# Processor.net
KiCad netlist of a schematic drawn in Altium Designer
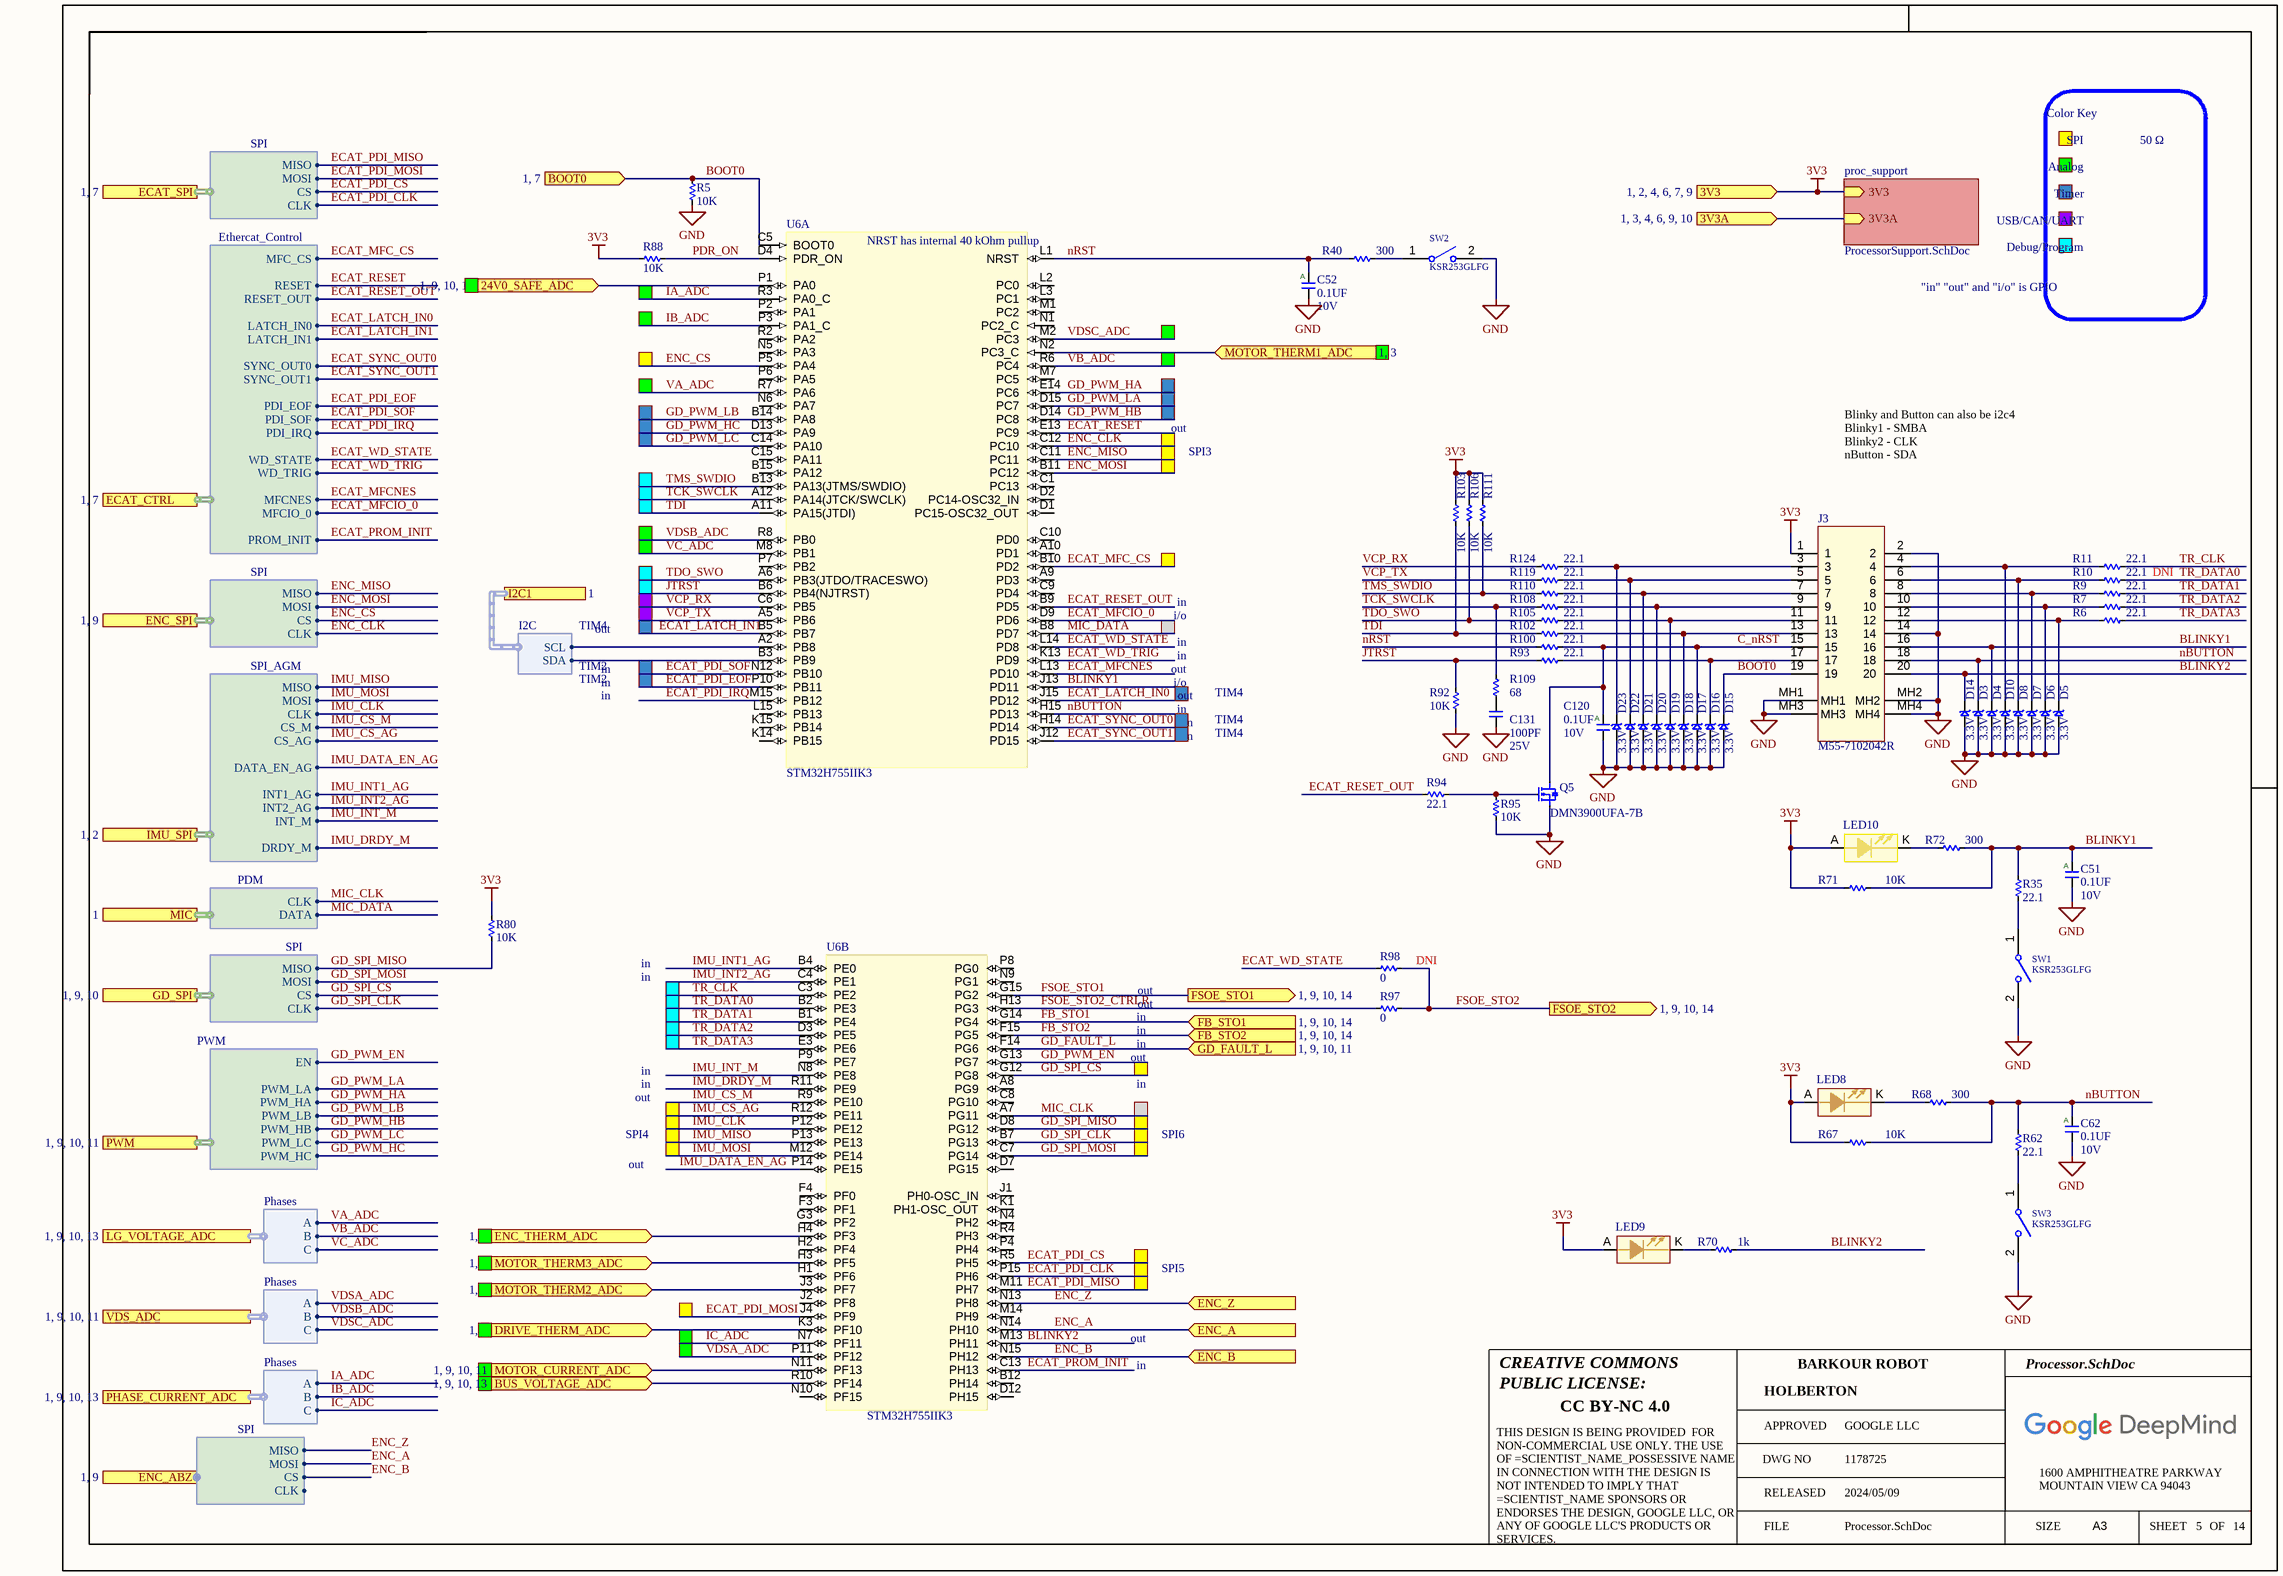
[diagram p0: Processor.SchDoc]

(export (version "E")
  (design (tool "Eeschema 10.0.6"))
  (components
    (comp (ref "C51")
      (value "0.1UF")
      (footprint "C0201")
      (description "CAP, CER, X6S, 0.1uF, 10V, 10%, 0201, AUTOGRADE")
      (fields
        (field (name "MFG") "MURATA")
        (field (name "VOLTAGE") "10V")
        (field (name "Comment") "__Template_Cap_Auto")
      )
      (libsource (lib "AltiumReleaseLibDB") (part "__Template_Cap_Auto"))
    )
    (comp (ref "C52")
      (value "0.1UF")
      (footprint "C0201")
      (description "CAP, CER, X6S, 0.1uF, 10V, 10%, 0201, AUTOGRADE")
      (fields
        (field (name "MFG") "MURATA")
        (field (name "VOLTAGE") "10V")
        (field (name "Comment") "__Template_Cap_Auto")
      )
      (libsource (lib "AltiumReleaseLibDB") (part "__Template_Cap_Auto"))
    )
    (comp (ref "C62")
      (value "0.1UF")
      (footprint "C0201")
      (description "CAP, CER, X6S, 0.1uF, 10V, 10%, 0201, AUTOGRADE")
      (fields
        (field (name "MFG") "MURATA")
        (field (name "VOLTAGE") "10V")
        (field (name "Comment") "__Template_Cap_Auto")
      )
      (libsource (lib "AltiumReleaseLibDB") (part "__Template_Cap_Auto"))
    )
    (comp (ref "C120")
      (value "0.1UF")
      (footprint "C0201")
      (description "CAP, CER, X6S, 0.1uF, 10V, 10%, 0201, AUTOGRADE")
      (fields
        (field (name "MFG") "MURATA")
        (field (name "VOLTAGE") "10V")
        (field (name "Comment") "__Template_Cap_Auto")
      )
      (libsource (lib "AltiumReleaseLibDB") (part "__Template_Cap_Auto"))
    )
    (comp (ref "C131")
      (value "100PF")
      (footprint "C0201")
      (description "CAP, CER, X7R, 100pF, 25V, 10%, 0201, 0.33mm T")
      (fields
        (field (name "MFG") "MURATA")
        (field (name "VOLTAGE") "25V")
        (field (name "Comment") "__Template_Cap")
      )
      (libsource (lib "AltiumReleaseLibDB") (part "__Template_Cap"))
    )
    (comp (ref "D3")
      (value "3.3V")
      (footprint "SOD1060X40")
      (description "TVS, DIODE, UNIDIR, 3.3VRWM, 4.8VBR, 7.8VCL, SOD-923")
      (fields (field (name "MFG") "ON Semiconductor"))
      (libsource (lib "AltiumReleaseLibDB") (part "__Template_Diode_TVS_A/K"))
    )
    (comp (ref "D4")
      (value "3.3V")
      (footprint "SOD1060X40")
      (description "TVS, DIODE, UNIDIR, 3.3VRWM, 4.8VBR, 7.8VCL, SOD-923")
      (fields (field (name "MFG") "ON Semiconductor"))
      (libsource (lib "AltiumReleaseLibDB") (part "__Template_Diode_TVS_A/K"))
    )
    (comp (ref "D5")
      (value "3.3V")
      (footprint "SOD1060X40")
      (description "TVS, DIODE, UNIDIR, 3.3VRWM, 4.8VBR, 7.8VCL, SOD-923")
      (fields (field (name "MFG") "ON Semiconductor"))
      (libsource (lib "AltiumReleaseLibDB") (part "__Template_Diode_TVS_A/K"))
    )
    (comp (ref "D6")
      (value "3.3V")
      (footprint "SOD1060X40")
      (description "TVS, DIODE, UNIDIR, 3.3VRWM, 4.8VBR, 7.8VCL, SOD-923")
      (fields (field (name "MFG") "ON Semiconductor"))
      (libsource (lib "AltiumReleaseLibDB") (part "__Template_Diode_TVS_A/K"))
    )
    (comp (ref "D7")
      (value "3.3V")
      (footprint "SOD1060X40")
      (description "TVS, DIODE, UNIDIR, 3.3VRWM, 4.8VBR, 7.8VCL, SOD-923")
      (fields (field (name "MFG") "ON Semiconductor"))
      (libsource (lib "AltiumReleaseLibDB") (part "__Template_Diode_TVS_A/K"))
    )
    (comp (ref "D8")
      (value "3.3V")
      (footprint "SOD1060X40")
      (description "TVS, DIODE, UNIDIR, 3.3VRWM, 4.8VBR, 7.8VCL, SOD-923")
      (fields (field (name "MFG") "ON Semiconductor"))
      (libsource (lib "AltiumReleaseLibDB") (part "__Template_Diode_TVS_A/K"))
    )
    (comp (ref "D10")
      (value "3.3V")
      (footprint "SOD1060X40")
      (description "TVS, DIODE, UNIDIR, 3.3VRWM, 4.8VBR, 7.8VCL, SOD-923")
      (fields (field (name "MFG") "ON Semiconductor"))
      (libsource (lib "AltiumReleaseLibDB") (part "__Template_Diode_TVS_A/K"))
    )
    (comp (ref "D14")
      (value "3.3V")
      (footprint "SOD1060X40")
      (description "TVS, DIODE, UNIDIR, 3.3VRWM, 4.8VBR, 7.8VCL, SOD-923")
      (fields (field (name "MFG") "ON Semiconductor"))
      (libsource (lib "AltiumReleaseLibDB") (part "__Template_Diode_TVS_A/K"))
    )
    (comp (ref "D15")
      (value "3.3V")
      (footprint "SOD1060X40")
      (description "TVS, DIODE, UNIDIR, 3.3VRWM, 4.8VBR, 7.8VCL, SOD-923")
      (fields (field (name "MFG") "ON Semiconductor"))
      (libsource (lib "AltiumReleaseLibDB") (part "__Template_Diode_TVS_A/K"))
    )
    (comp (ref "D16")
      (value "3.3V")
      (footprint "SOD1060X40")
      (description "TVS, DIODE, UNIDIR, 3.3VRWM, 4.8VBR, 7.8VCL, SOD-923")
      (fields (field (name "MFG") "ON Semiconductor"))
      (libsource (lib "AltiumReleaseLibDB") (part "__Template_Diode_TVS_A/K"))
    )
    (comp (ref "D17")
      (value "3.3V")
      (footprint "SOD1060X40")
      (description "TVS, DIODE, UNIDIR, 3.3VRWM, 4.8VBR, 7.8VCL, SOD-923")
      (fields (field (name "MFG") "ON Semiconductor"))
      (libsource (lib "AltiumReleaseLibDB") (part "__Template_Diode_TVS_A/K"))
    )
    (comp (ref "D18")
      (value "3.3V")
      (footprint "SOD1060X40")
      (description "TVS, DIODE, UNIDIR, 3.3VRWM, 4.8VBR, 7.8VCL, SOD-923")
      (fields (field (name "MFG") "ON Semiconductor"))
      (libsource (lib "AltiumReleaseLibDB") (part "__Template_Diode_TVS_A/K"))
    )
    (comp (ref "D19")
      (value "3.3V")
      (footprint "SOD1060X40")
      (description "TVS, DIODE, UNIDIR, 3.3VRWM, 4.8VBR, 7.8VCL, SOD-923")
      (fields (field (name "MFG") "ON Semiconductor"))
      (libsource (lib "AltiumReleaseLibDB") (part "__Template_Diode_TVS_A/K"))
    )
    (comp (ref "D20")
      (value "3.3V")
      (footprint "SOD1060X40")
      (description "TVS, DIODE, UNIDIR, 3.3VRWM, 4.8VBR, 7.8VCL, SOD-923")
      (fields (field (name "MFG") "ON Semiconductor"))
      (libsource (lib "AltiumReleaseLibDB") (part "__Template_Diode_TVS_A/K"))
    )
    (comp (ref "D21")
      (value "3.3V")
      (footprint "SOD1060X40")
      (description "TVS, DIODE, UNIDIR, 3.3VRWM, 4.8VBR, 7.8VCL, SOD-923")
      (fields (field (name "MFG") "ON Semiconductor"))
      (libsource (lib "AltiumReleaseLibDB") (part "__Template_Diode_TVS_A/K"))
    )
    (comp (ref "D22")
      (value "3.3V")
      (footprint "SOD1060X40")
      (description "TVS, DIODE, UNIDIR, 3.3VRWM, 4.8VBR, 7.8VCL, SOD-923")
      (fields (field (name "MFG") "ON Semiconductor"))
      (libsource (lib "AltiumReleaseLibDB") (part "__Template_Diode_TVS_A/K"))
    )
    (comp (ref "D23")
      (value "3.3V")
      (footprint "SOD1060X40")
      (description "TVS, DIODE, UNIDIR, 3.3VRWM, 4.8VBR, 7.8VCL, SOD-923")
      (fields (field (name "MFG") "ON Semiconductor"))
      (libsource (lib "AltiumReleaseLibDB") (part "__Template_Diode_TVS_A/K"))
    )
    (comp (ref "J3")
      (value "M55-7102042R")
      (footprint "CON_M55-7102042R")
      (description "CONN HEADER SMD R/A 20POS 1.27MM")
      (fields (field (name "MFG") "Harwin Inc.") (field (name "MFG P/N") "M55-7102042R"))
      (libsource (lib "AltiumReleaseLibDB") (part "__Template_Connector_2X10_4MH"))
    )
    (comp (ref "LED8")
      (value "__Template_LED_ORANGE_AK")
      (footprint "LED_APG0603SYC-TT")
      (description "LED, ORANGE, 611NM, 10mA, CLEAR, 0201")
      (fields (field (name "MFG") "Kingbright"))
      (libsource (lib "AltiumReleaseLibDB") (part "__Template_LED_ORANGE_AK"))
    )
    (comp (ref "LED9")
      (value "__Template_LED_ORANGE_AK")
      (footprint "LED_APG0603SYC-TT")
      (description "LED, ORANGE, 611NM, 10mA, CLEAR, 0201")
      (fields (field (name "MFG") "Kingbright"))
      (libsource (lib "AltiumReleaseLibDB") (part "__Template_LED_ORANGE_AK"))
    )
    (comp (ref "LED10")
      (value "__Template_LED_YELLOW_AK")
      (footprint "LED_APG0603SYC-TT")
      (description "LED, YELLOW, 591NM, 10mA, CLEAR, 0201")
      (fields (field (name "MFG") "Kingbright"))
      (libsource (lib "AltiumReleaseLibDB") (part "__Template_LED_YELLOW_AK"))
    )
    (comp (ref "Q5")
      (value "NFET_DMN3900UFA")
      (footprint "3XDFN")
      (description "MOSFET, N-CH, 30V, 0.55A, DMN3900")
      (fields (field (name "MFG") "Diodes Incorporated") (field (name "MFG P/N") "DMN3900UFA-7B"))
      (libsource (lib "AltiumReleaseLibDB") (part "NFET_DMN3900UFA"))
    )
    (comp (ref "R5")
      (value "10K")
      (footprint "R0201")
      (description "RES, 10K, 1%, 1/20W, 0201, AUTOGRADE")
      (fields (field (name "MFG") "PANASONIC") (field (name "Comment") "__Template_Resistor"))
      (libsource (lib "AltiumReleaseLibDB") (part "__Template_Resistor"))
    )
    (comp (ref "R6")
      (value "22.1")
      (footprint "R0201")
      (description "RES, 22.1, 1%, 1/20W, 0201, AUTOGRADE")
      (fields
        (field (name "MFG") "Panasonic Electronic Components")
        (field (name "Comment") "__Template_Resistor")
      )
      (libsource (lib "AltiumReleaseLibDB") (part "__Template_Resistor"))
    )
    (comp (ref "R7")
      (value "22.1")
      (footprint "R0201")
      (description "RES, 22.1, 1%, 1/20W, 0201, AUTOGRADE")
      (fields
        (field (name "MFG") "Panasonic Electronic Components")
        (field (name "Comment") "__Template_Resistor")
      )
      (libsource (lib "AltiumReleaseLibDB") (part "__Template_Resistor"))
    )
    (comp (ref "R9")
      (value "22.1")
      (footprint "R0201")
      (description "RES, 22.1, 1%, 1/20W, 0201, AUTOGRADE")
      (fields
        (field (name "MFG") "Panasonic Electronic Components")
        (field (name "Comment") "__Template_Resistor")
      )
      (libsource (lib "AltiumReleaseLibDB") (part "__Template_Resistor"))
    )
    (comp (ref "R10")
      (value "22.1")
      (footprint "R0201")
      (description "RES, 22.1, 1%, 1/20W, 0201, AUTOGRADE")
      (fields
        (field (name "MFG") "Panasonic Electronic Components")
        (field (name "DNI") "DNI")
        (field (name "Comment") "__Template_Resistor")
      )
      (libsource (lib "AltiumReleaseLibDB") (part "__Template_Resistor"))
    )
    (comp (ref "R11")
      (value "22.1")
      (footprint "R0201")
      (description "RES, 22.1, 1%, 1/20W, 0201, AUTOGRADE")
      (fields
        (field (name "MFG") "Panasonic Electronic Components")
        (field (name "Comment") "__Template_Resistor")
      )
      (libsource (lib "AltiumReleaseLibDB") (part "__Template_Resistor"))
    )
    (comp (ref "R35")
      (value "22.1")
      (footprint "R0201")
      (description "RES, 22.1, 1%, 1/20W, 0201, AUTOGRADE")
      (fields
        (field (name "MFG") "Panasonic Electronic Components")
        (field (name "Comment") "__Template_Resistor")
      )
      (libsource (lib "AltiumReleaseLibDB") (part "__Template_Resistor"))
    )
    (comp (ref "R40")
      (value "300")
      (footprint "R0201")
      (description "RES, 300, 1%, 1/20W, 0201, AUTOGRADE")
      (fields
        (field (name "MFG") "Panasonic Electronic Components")
        (field (name "Comment") "__Template_Resistor")
      )
      (libsource (lib "AltiumReleaseLibDB") (part "__Template_Resistor"))
    )
    (comp (ref "R62")
      (value "22.1")
      (footprint "R0201")
      (description "RES, 22.1, 1%, 1/20W, 0201, AUTOGRADE")
      (fields
        (field (name "MFG") "Panasonic Electronic Components")
        (field (name "Comment") "__Template_Resistor")
      )
      (libsource (lib "AltiumReleaseLibDB") (part "__Template_Resistor"))
    )
    (comp (ref "R67")
      (value "10K")
      (footprint "R0201")
      (description "RES, 10K, 1%, 1/20W, 0201, AUTOGRADE")
      (fields (field (name "MFG") "PANASONIC") (field (name "Comment") "__Template_Resistor"))
      (libsource (lib "AltiumReleaseLibDB") (part "__Template_Resistor"))
    )
    (comp (ref "R68")
      (value "300")
      (footprint "R0201")
      (description "RES, 300, 1%, 1/20W, 0201, AUTOGRADE")
      (fields
        (field (name "MFG") "Panasonic Electronic Components")
        (field (name "Comment") "__Template_Resistor")
      )
      (libsource (lib "AltiumReleaseLibDB") (part "__Template_Resistor"))
    )
    (comp (ref "R70")
      (value "1k")
      (footprint "R0201")
      (description "RES, 1K, 1%, 1/20W, 0201, AUTOGRADE")
      (fields (field (name "MFG") "Bourns Inc.") (field (name "Comment") "__Template_Resistor"))
      (libsource (lib "AltiumReleaseLibDB") (part "__Template_Resistor"))
    )
    (comp (ref "R71")
      (value "10K")
      (footprint "R0201")
      (description "RES, 10K, 1%, 1/20W, 0201, AUTOGRADE")
      (fields (field (name "MFG") "PANASONIC") (field (name "Comment") "__Template_Resistor"))
      (libsource (lib "AltiumReleaseLibDB") (part "__Template_Resistor"))
    )
    (comp (ref "R72")
      (value "300")
      (footprint "R0201")
      (description "RES, 300, 1%, 1/20W, 0201, AUTOGRADE")
      (fields
        (field (name "MFG") "Panasonic Electronic Components")
        (field (name "Comment") "__Template_Resistor")
      )
      (libsource (lib "AltiumReleaseLibDB") (part "__Template_Resistor"))
    )
    (comp (ref "R80")
      (value "10K")
      (footprint "R0201")
      (description "RES, 10K, 1%, 1/20W, 0201, AUTOGRADE")
      (fields (field (name "MFG") "PANASONIC") (field (name "Comment") "__Template_Resistor"))
      (libsource (lib "AltiumReleaseLibDB") (part "__Template_Resistor"))
    )
    (comp (ref "R88")
      (value "10K")
      (footprint "R0201")
      (description "RES, 10K, 1%, 1/20W, 0201, AUTOGRADE")
      (fields (field (name "MFG") "PANASONIC") (field (name "Comment") "__Template_Resistor"))
      (libsource (lib "AltiumReleaseLibDB") (part "__Template_Resistor"))
    )
    (comp (ref "R92")
      (value "10K")
      (footprint "R0201")
      (description "RES, 10K, 1%, 1/20W, 0201, AUTOGRADE")
      (fields (field (name "MFG") "PANASONIC") (field (name "Comment") "__Template_Resistor"))
      (libsource (lib "AltiumReleaseLibDB") (part "__Template_Resistor"))
    )
    (comp (ref "R93")
      (value "22.1")
      (footprint "R0201")
      (description "RES, 22.1, 1%, 1/20W, 0201, AUTOGRADE")
      (fields
        (field (name "MFG") "Panasonic Electronic Components")
        (field (name "Comment") "__Template_Resistor")
      )
      (libsource (lib "AltiumReleaseLibDB") (part "__Template_Resistor"))
    )
    (comp (ref "R94")
      (value "22.1")
      (footprint "R0201")
      (description "RES, 22.1, 1%, 1/20W, 0201, AUTOGRADE")
      (fields
        (field (name "MFG") "Panasonic Electronic Components")
        (field (name "Comment") "__Template_Resistor")
      )
      (libsource (lib "AltiumReleaseLibDB") (part "__Template_Resistor"))
    )
    (comp (ref "R95")
      (value "10K")
      (footprint "R0201")
      (description "RES, 10K, 1%, 1/20W, 0201, AUTOGRADE")
      (fields (field (name "MFG") "PANASONIC") (field (name "Comment") "__Template_Resistor"))
      (libsource (lib "AltiumReleaseLibDB") (part "__Template_Resistor"))
    )
    (comp (ref "R97")
      (value "0")
      (footprint "R0402")
      (description "RES, 0, JUMPER, 1/16W, 0402")
      (fields (field (name "MFG") "YAGEO"))
      (libsource (lib "AltiumReleaseLibDB") (part "__Template_Resistor"))
    )
    (comp (ref "R98")
      (value "0")
      (footprint "R0402")
      (description "RES, 0, JUMPER, 1/16W, 0402")
      (fields (field (name "MFG") "YAGEO") (field (name "DNI") "DNI"))
      (libsource (lib "AltiumReleaseLibDB") (part "__Template_Resistor"))
    )
    (comp (ref "R100")
      (value "22.1")
      (footprint "R0201")
      (description "RES, 22.1, 1%, 1/20W, 0201, AUTOGRADE")
      (fields
        (field (name "MFG") "Panasonic Electronic Components")
        (field (name "Comment") "__Template_Resistor")
      )
      (libsource (lib "AltiumReleaseLibDB") (part "__Template_Resistor"))
    )
    (comp (ref "R102")
      (value "22.1")
      (footprint "R0201")
      (description "RES, 22.1, 1%, 1/20W, 0201, AUTOGRADE")
      (fields
        (field (name "MFG") "Panasonic Electronic Components")
        (field (name "Comment") "__Template_Resistor")
      )
      (libsource (lib "AltiumReleaseLibDB") (part "__Template_Resistor"))
    )
    (comp (ref "R103")
      (value "10K")
      (footprint "R0201")
      (description "RES, 10K, 1%, 1/20W, 0201, AUTOGRADE")
      (fields (field (name "MFG") "PANASONIC") (field (name "Comment") "__Template_Resistor"))
      (libsource (lib "AltiumReleaseLibDB") (part "__Template_Resistor"))
    )
    (comp (ref "R105")
      (value "22.1")
      (footprint "R0201")
      (description "RES, 22.1, 1%, 1/20W, 0201, AUTOGRADE")
      (fields
        (field (name "MFG") "Panasonic Electronic Components")
        (field (name "Comment") "__Template_Resistor")
      )
      (libsource (lib "AltiumReleaseLibDB") (part "__Template_Resistor"))
    )
    (comp (ref "R106")
      (value "10K")
      (footprint "R0201")
      (description "RES, 10K, 1%, 1/20W, 0201, AUTOGRADE")
      (fields (field (name "MFG") "PANASONIC") (field (name "Comment") "__Template_Resistor"))
      (libsource (lib "AltiumReleaseLibDB") (part "__Template_Resistor"))
    )
    (comp (ref "R108")
      (value "22.1")
      (footprint "R0201")
      (description "RES, 22.1, 1%, 1/20W, 0201, AUTOGRADE")
      (fields
        (field (name "MFG") "Panasonic Electronic Components")
        (field (name "Comment") "__Template_Resistor")
      )
      (libsource (lib "AltiumReleaseLibDB") (part "__Template_Resistor"))
    )
    (comp (ref "R109")
      (value "68")
      (footprint "R0201")
      (description "RES, 68, 1%, 1/20W, 0201, AUTOGRADE")
      (fields
        (field (name "MFG") "Panasonic Electronic Components")
        (field (name "Comment") "__Template_Resistor")
      )
      (libsource (lib "AltiumReleaseLibDB") (part "__Template_Resistor"))
    )
    (comp (ref "R110")
      (value "22.1")
      (footprint "R0201")
      (description "RES, 22.1, 1%, 1/20W, 0201, AUTOGRADE")
      (fields
        (field (name "MFG") "Panasonic Electronic Components")
        (field (name "Comment") "__Template_Resistor")
      )
      (libsource (lib "AltiumReleaseLibDB") (part "__Template_Resistor"))
    )
    (comp (ref "R111")
      (value "10K")
      (footprint "R0201")
      (description "RES, 10K, 1%, 1/20W, 0201, AUTOGRADE")
      (fields (field (name "MFG") "PANASONIC") (field (name "Comment") "__Template_Resistor"))
      (libsource (lib "AltiumReleaseLibDB") (part "__Template_Resistor"))
    )
    (comp (ref "R119")
      (value "22.1")
      (footprint "R0201")
      (description "RES, 22.1, 1%, 1/20W, 0201, AUTOGRADE")
      (fields
        (field (name "MFG") "Panasonic Electronic Components")
        (field (name "Comment") "__Template_Resistor")
      )
      (libsource (lib "AltiumReleaseLibDB") (part "__Template_Resistor"))
    )
    (comp (ref "R124")
      (value "22.1")
      (footprint "R0201")
      (description "RES, 22.1, 1%, 1/20W, 0201, AUTOGRADE")
      (fields
        (field (name "MFG") "Panasonic Electronic Components")
        (field (name "Comment") "__Template_Resistor")
      )
      (libsource (lib "AltiumReleaseLibDB") (part "__Template_Resistor"))
    )
    (comp (ref "SW1")
      (value "KSR253GLFG")
      (footprint "SW_KSR253GLFG")
      (description "SWITCH TACTILE SPST-NO 0.01A 32V")
      (fields (field (name "MFG") "C&K"))
      (libsource (lib "Cortes_Gebru_v05_Rev03") (part "SW_2P-KSR253GLFG"))
    )
    (comp (ref "SW2")
      (value "KSR253GLFG")
      (footprint "SW_KSR253GLFG")
      (description "SWITCH TACTILE SPST-NO 0.01A 32V")
      (fields (field (name "MFG") "C&K"))
      (libsource (lib "Cortes_Gebru_v05_Rev03") (part "SW_2P-KSR253GLFG"))
    )
    (comp (ref "SW3")
      (value "KSR253GLFG")
      (footprint "SW_KSR253GLFG")
      (description "SWITCH TACTILE SPST-NO 0.01A 32V")
      (fields (field (name "MFG") "C&K"))
      (libsource (lib "Cortes_Gebru_v05_Rev03") (part "SW_2P-KSR253GLFG"))
    )
    (comp (ref "U6")
      (value "MCU_STM32H755IIK3")
      (footprint "BGS201C65P15X15_1000X1000X60")
      (description "IC, MCU, STM32H755xI, ARM, 32-BIT, 240MHZ, 128 I/O, 2MB, FLASH, 1.62V TO 3.6V, UFBGA-201")
      (fields (field (name "MFG") "STMicroelectronics") (field (name "MFG P/N") "STM32H755IIK3"))
      (libsource (lib "AltiumReleaseLibDB") (part "MCU_STM32H755IIK3"))
    )
  )
  (nets
    (net (code "9") (name "/24V0_SAFE_ADC") (class "Default")
      (node (ref "U6") (pin "P1") (pinfunction "PA0_P1") (pintype "bidirectional"))
    )
    (net (code "10") (name "/BLINKY1") (class "Default")
      (node (ref "C51") (pin "1") (pintype "passive"))
      (node (ref "D4") (pin "K") (pinfunction "K_K") (pintype "passive"))
      (node (ref "J3") (pin "16") (pinfunction "16_16") (pintype "passive"))
      (node (ref "R35") (pin "1") (pintype "passive"))
      (node (ref "R71") (pin "1") (pintype "passive"))
      (node (ref "R72") (pin "2") (pintype "passive"))
      (node (ref "U6") (pin "J13") (pinfunction "PD11_J13") (pintype "bidirectional"))
    )
    (net (code "11") (name "/BLINKY2") (class "Default")
      (node (ref "D14") (pin "K") (pinfunction "K_K") (pintype "passive"))
      (node (ref "J3") (pin "20") (pinfunction "20_20") (pintype "passive"))
      (node (ref "R70") (pin "2") (pintype "passive"))
      (node (ref "U6") (pin "M13") (pinfunction "PH11_M13") (pintype "bidirectional"))
    )
    (net (code "12") (name "/BOOT0") (class "Default")
      (node (ref "D15") (pin "K") (pinfunction "K_K") (pintype "passive"))
      (node (ref "J3") (pin "19") (pinfunction "19_19") (pintype "passive"))
      (node (ref "R5") (pin "2") (pintype "passive"))
      (node (ref "U6") (pin "C5") (pinfunction "BOOT0_C5") (pintype "input"))
    )
    (net (code "13") (name "/BUS_VOLTAGE_ADC") (class "Default")
      (node (ref "U6") (pin "R10") (pinfunction "PF14_R10") (pintype "bidirectional"))
    )
    (net (code "14") (name "/C_nRST") (class "Default")
      (node (ref "C120") (pin "1") (pintype "passive"))
      (node (ref "D17") (pin "K") (pinfunction "K_K") (pintype "passive"))
      (node (ref "J3") (pin "15") (pinfunction "15_15") (pintype "passive"))
      (node (ref "Q5") (pin "3") (pinfunction "D_3") (pintype "passive"))
      (node (ref "R100") (pin "2") (pintype "passive"))
    )
    (net (code "15") (name "/DRIVE_THERM_ADC") (class "Default")
      (node (ref "U6") (pin "K3") (pinfunction "PF10_K3") (pintype "bidirectional"))
    )
    (net (code "16") (name "/ECAT_LATCH_IN0") (class "Default")
      (node (ref "U6") (pin "J15") (pinfunction "PD12_J15") (pintype "bidirectional"))
    )
    (net (code "17") (name "/ECAT_LATCH_IN1") (class "Default")
      (node (ref "U6") (pin "B5") (pinfunction "PB7_B5") (pintype "bidirectional"))
    )
    (net (code "18") (name "/ECAT_MFCIO_0") (class "Default")
      (node (ref "U6") (pin "D9") (pinfunction "PD6_D9") (pintype "bidirectional"))
    )
    (net (code "19") (name "/ECAT_MFCNES") (class "Default")
      (node (ref "U6") (pin "L13") (pinfunction "PD10_L13") (pintype "bidirectional"))
    )
    (net (code "20") (name "/ECAT_MFC_CS") (class "Default")
      (node (ref "U6") (pin "B10") (pinfunction "PD2_B10") (pintype "bidirectional"))
    )
    (net (code "21") (name "/ECAT_PDI_CLK") (class "Default")
      (node (ref "U6") (pin "P15") (pinfunction "PH6_P15") (pintype "bidirectional"))
    )
    (net (code "22") (name "/ECAT_PDI_CS") (class "Default")
      (node (ref "U6") (pin "R5") (pinfunction "PH5_R5") (pintype "bidirectional"))
    )
    (net (code "23") (name "/ECAT_PDI_EOF") (class "Default")
      (node (ref "U6") (pin "P10") (pinfunction "PB11_P10") (pintype "bidirectional"))
    )
    (net (code "24") (name "/ECAT_PDI_IRQ") (class "Default")
      (node (ref "U6") (pin "M15") (pinfunction "PB12_M15") (pintype "bidirectional"))
    )
    (net (code "25") (name "/ECAT_PDI_MISO") (class "Default")
      (node (ref "U6") (pin "M11") (pinfunction "PH7_M11") (pintype "bidirectional"))
    )
    (net (code "26") (name "/ECAT_PDI_MOSI") (class "Default")
      (node (ref "U6") (pin "J4") (pinfunction "PF9_J4") (pintype "bidirectional"))
    )
    (net (code "27") (name "/ECAT_PDI_SOF") (class "Default")
      (node (ref "U6") (pin "N12") (pinfunction "PB10_N12") (pintype "bidirectional"))
    )
    (net (code "28") (name "/ECAT_PROM_INIT") (class "Default")
      (node (ref "U6") (pin "C13") (pinfunction "PH13_C13") (pintype "bidirectional"))
    )
    (net (code "29") (name "/ECAT_RESET") (class "Default")
      (node (ref "U6") (pin "E13") (pinfunction "PC9_E13") (pintype "bidirectional"))
    )
    (net (code "30") (name "/ECAT_RESET_OUT") (class "Default")
      (node (ref "R94") (pin "1") (pintype "passive"))
      (node (ref "U6") (pin "B9") (pinfunction "PD5_B9") (pintype "bidirectional"))
    )
    (net (code "31") (name "/ECAT_SYNC_OUT0") (class "Default")
      (node (ref "U6") (pin "H14") (pinfunction "PD14_H14") (pintype "bidirectional"))
    )
    (net (code "32") (name "/ECAT_SYNC_OUT1") (class "Default")
      (node (ref "U6") (pin "J12") (pinfunction "PD15_J12") (pintype "bidirectional"))
    )
    (net (code "33") (name "/ECAT_WD_STATE") (class "Default")
      (node (ref "R98") (pin "2") (pintype "passive"))
      (node (ref "U6") (pin "L14") (pinfunction "PD8_L14") (pintype "bidirectional"))
    )
    (net (code "34") (name "/ECAT_WD_TRIG") (class "Default")
      (node (ref "U6") (pin "K13") (pinfunction "PD9_K13") (pintype "bidirectional"))
    )
    (net (code "35") (name "/ENC_A") (class "Default")
      (node (ref "U6") (pin "N14") (pinfunction "PH10_N14") (pintype "bidirectional"))
    )
    (net (code "36") (name "/ENC_B") (class "Default")
      (node (ref "U6") (pin "N15") (pinfunction "PH12_N15") (pintype "bidirectional"))
    )
    (net (code "37") (name "/ENC_CLK") (class "Default")
      (node (ref "U6") (pin "C12") (pinfunction "PC10_C12") (pintype "bidirectional"))
    )
    (net (code "38") (name "/ENC_CS") (class "Default")
      (node (ref "U6") (pin "P5") (pinfunction "PA4_P5") (pintype "bidirectional"))
    )
    (net (code "39") (name "/ENC_MISO") (class "Default")
      (node (ref "U6") (pin "C11") (pinfunction "PC11_C11") (pintype "bidirectional"))
    )
    (net (code "40") (name "/ENC_MOSI") (class "Default")
      (node (ref "U6") (pin "B11") (pinfunction "PC12_B11") (pintype "bidirectional"))
    )
    (net (code "41") (name "/ENC_THERM_ADC") (class "Default")
      (node (ref "U6") (pin "H4") (pinfunction "PF3_H4") (pintype "bidirectional"))
    )
    (net (code "42") (name "/ENC_Z") (class "Default")
      (node (ref "U6") (pin "N13") (pinfunction "PH8_N13") (pintype "bidirectional"))
    )
    (net (code "43") (name "/FB_STO1") (class "Default")
      (node (ref "U6") (pin "G14") (pinfunction "PG4_G14") (pintype "bidirectional"))
    )
    (net (code "44") (name "/FB_STO2") (class "Default")
      (node (ref "U6") (pin "F15") (pinfunction "PG5_F15") (pintype "bidirectional"))
    )
    (net (code "45") (name "/FSOE_STO1") (class "Default")
      (node (ref "U6") (pin "G15") (pinfunction "PG2_G15") (pintype "bidirectional"))
    )
    (net (code "46") (name "/FSOE_STO2") (class "Default")
      (node (ref "R97") (pin "1") (pintype "passive"))
      (node (ref "R98") (pin "1") (pintype "passive"))
    )
    (net (code "47") (name "/FSOE_STO2_CTRLR") (class "Default")
      (node (ref "R97") (pin "2") (pintype "passive"))
      (node (ref "U6") (pin "H13") (pinfunction "PG3_H13") (pintype "bidirectional"))
    )
    (net (code "48") (name "/GD_FAULT_L") (class "Default")
      (node (ref "U6") (pin "F14") (pinfunction "PG6_F14") (pintype "bidirectional"))
    )
    (net (code "49") (name "/GD_PWM_EN") (class "Default")
      (node (ref "U6") (pin "G13") (pinfunction "PG7_G13") (pintype "bidirectional"))
    )
    (net (code "50") (name "/GD_PWM_HA") (class "Default")
      (node (ref "U6") (pin "E14") (pinfunction "PC6_E14") (pintype "bidirectional"))
    )
    (net (code "51") (name "/GD_PWM_HB") (class "Default")
      (node (ref "U6") (pin "D14") (pinfunction "PC8_D14") (pintype "bidirectional"))
    )
    (net (code "52") (name "/GD_PWM_HC") (class "Default")
      (node (ref "U6") (pin "D13") (pinfunction "PA9_D13") (pintype "bidirectional"))
    )
    (net (code "53") (name "/GD_PWM_LA") (class "Default")
      (node (ref "U6") (pin "D15") (pinfunction "PC7_D15") (pintype "bidirectional"))
    )
    (net (code "54") (name "/GD_PWM_LB") (class "Default")
      (node (ref "U6") (pin "B14") (pinfunction "PA8_B14") (pintype "bidirectional"))
    )
    (net (code "55") (name "/GD_PWM_LC") (class "Default")
      (node (ref "U6") (pin "C14") (pinfunction "PA10_C14") (pintype "bidirectional"))
    )
    (net (code "56") (name "/GD_SPI_CLK") (class "Default")
      (node (ref "U6") (pin "B7") (pinfunction "PG13_B7") (pintype "bidirectional"))
    )
    (net (code "57") (name "/GD_SPI_CS") (class "Default")
      (node (ref "U6") (pin "G12") (pinfunction "PG8_G12") (pintype "bidirectional"))
    )
    (net (code "58") (name "/GD_SPI_MISO") (class "Default")
      (node (ref "R80") (pin "1") (pintype "passive"))
      (node (ref "U6") (pin "D8") (pinfunction "PG12_D8") (pintype "bidirectional"))
    )
    (net (code "59") (name "/GD_SPI_MOSI") (class "Default")
      (node (ref "U6") (pin "C7") (pinfunction "PG14_C7") (pintype "bidirectional"))
    )
    (net (code "60") (name "/IA_ADC") (class "Default")
      (node (ref "U6") (pin "R3") (pinfunction "PA0_C_R3") (pintype "input"))
    )
    (net (code "61") (name "/IB_ADC") (class "Default")
      (node (ref "U6") (pin "P3") (pinfunction "PA1_C_P3") (pintype "input"))
    )
    (net (code "62") (name "/IC_ADC") (class "Default")
      (node (ref "U6") (pin "N7") (pinfunction "PF11_N7") (pintype "bidirectional"))
    )
    (net (code "63") (name "/IMU_CLK") (class "Default")
      (node (ref "U6") (pin "P12") (pinfunction "PE12_P12") (pintype "bidirectional"))
    )
    (net (code "64") (name "/IMU_CS_AG") (class "Default")
      (node (ref "U6") (pin "R12") (pinfunction "PE11_R12") (pintype "bidirectional"))
    )
    (net (code "65") (name "/IMU_CS_M") (class "Default")
      (node (ref "U6") (pin "R9") (pinfunction "PE10_R9") (pintype "bidirectional"))
    )
    (net (code "66") (name "/IMU_DATA_EN_AG") (class "Default")
      (node (ref "U6") (pin "P14") (pinfunction "PE15_P14") (pintype "bidirectional"))
    )
    (net (code "67") (name "/IMU_DRDY_M") (class "Default")
      (node (ref "U6") (pin "R11") (pinfunction "PE9_R11") (pintype "bidirectional"))
    )
    (net (code "68") (name "/IMU_INT1_AG") (class "Default")
      (node (ref "U6") (pin "B4") (pinfunction "PE0_B4") (pintype "bidirectional"))
    )
    (net (code "69") (name "/IMU_INT2_AG") (class "Default")
      (node (ref "U6") (pin "C4") (pinfunction "PE1_C4") (pintype "bidirectional"))
    )
    (net (code "70") (name "/IMU_INT_M") (class "Default")
      (node (ref "U6") (pin "N8") (pinfunction "PE8_N8") (pintype "bidirectional"))
    )
    (net (code "71") (name "/IMU_MISO") (class "Default")
      (node (ref "U6") (pin "P13") (pinfunction "PE13_P13") (pintype "bidirectional"))
    )
    (net (code "72") (name "/IMU_MOSI") (class "Default")
      (node (ref "U6") (pin "M12") (pinfunction "PE14_M12") (pintype "bidirectional"))
    )
    (net (code "73") (name "/JTRST") (class "Default")
      (node (ref "R92") (pin "2") (pintype "passive"))
      (node (ref "R93") (pin "1") (pintype "passive"))
      (node (ref "U6") (pin "B6") (pinfunction "PB4(NJTRST)_B6") (pintype "bidirectional"))
    )
    (net (code "74") (name "/MIC_CLK") (class "Default")
      (node (ref "U6") (pin "A7") (pinfunction "PG11_A7") (pintype "bidirectional"))
    )
    (net (code "75") (name "/MIC_DATA") (class "Default")
      (node (ref "U6") (pin "B8") (pinfunction "PD7_B8") (pintype "bidirectional"))
    )
    (net (code "76") (name "/MOTOR_CURRENT_ADC") (class "Default")
      (node (ref "U6") (pin "N11") (pinfunction "PF13_N11") (pintype "bidirectional"))
    )
    (net (code "77") (name "/MOTOR_THERM1_ADC") (class "Default")
      (node (ref "U6") (pin "N2") (pinfunction "PC3_C_N2") (pintype "input"))
    )
    (net (code "78") (name "/MOTOR_THERM2_ADC") (class "Default")
      (node (ref "U6") (pin "J3") (pinfunction "PF7_J3") (pintype "bidirectional"))
    )
    (net (code "79") (name "/MOTOR_THERM3_ADC") (class "Default")
      (node (ref "U6") (pin "H3") (pinfunction "PF5_H3") (pintype "bidirectional"))
    )
    (net (code "80") (name "/PDR_ON") (class "Default")
      (node (ref "R88") (pin "1") (pintype "passive"))
      (node (ref "U6") (pin "D4") (pinfunction "PDR_ON_D4") (pintype "input"))
    )
    (net (code "81") (name "/SCL") (class "Default")
      (node (ref "U6") (pin "A2") (pinfunction "PB8_A2") (pintype "bidirectional"))
    )
    (net (code "82") (name "/SDA") (class "Default")
      (node (ref "U6") (pin "B3") (pinfunction "PB9_B3") (pintype "bidirectional"))
    )
    (net (code "83") (name "/TCK_SWCLK") (class "Default")
      (node (ref "R108") (pin "1") (pintype "passive"))
      (node (ref "R109") (pin "2") (pintype "passive"))
      (node (ref "U6") (pin "A12") (pinfunction "PA14(JTCK/SWCLK)_A12") (pintype "bidirectional"))
    )
    (net (code "84") (name "/TDI") (class "Default")
      (node (ref "R102") (pin "1") (pintype "passive"))
      (node (ref "R103") (pin "1") (pintype "passive"))
      (node (ref "U6") (pin "A11") (pinfunction "PA15(JTDI)_A11") (pintype "bidirectional"))
    )
    (net (code "85") (name "/TDO_SWO") (class "Default")
      (node (ref "R105") (pin "1") (pintype "passive"))
      (node (ref "R106") (pin "1") (pintype "passive"))
      (node (ref "U6") (pin "A6") (pinfunction "PB3(JTDO/TRACESWO)_A6") (pintype "bidirectional"))
    )
    (net (code "86") (name "/TMS_SWDIO") (class "Default")
      (node (ref "R110") (pin "1") (pintype "passive"))
      (node (ref "R111") (pin "1") (pintype "passive"))
      (node (ref "U6") (pin "B13") (pinfunction "PA13(JTMS/SWDIO)_B13") (pintype "bidirectional"))
    )
    (net (code "87") (name "/TR_CLK") (class "Default")
      (node (ref "R11") (pin "2") (pintype "passive"))
      (node (ref "U6") (pin "C3") (pinfunction "PE2_C3") (pintype "bidirectional"))
    )
    (net (code "88") (name "/TR_DATA0") (class "Default")
      (node (ref "R10") (pin "2") (pintype "passive"))
      (node (ref "U6") (pin "B2") (pinfunction "PE3_B2") (pintype "bidirectional"))
    )
    (net (code "89") (name "/TR_DATA1") (class "Default")
      (node (ref "R9") (pin "2") (pintype "passive"))
      (node (ref "U6") (pin "B1") (pinfunction "PE4_B1") (pintype "bidirectional"))
    )
    (net (code "90") (name "/TR_DATA2") (class "Default")
      (node (ref "R7") (pin "2") (pintype "passive"))
      (node (ref "U6") (pin "D3") (pinfunction "PE5_D3") (pintype "bidirectional"))
    )
    (net (code "91") (name "/TR_DATA3") (class "Default")
      (node (ref "R6") (pin "2") (pintype "passive"))
      (node (ref "U6") (pin "E3") (pinfunction "PE6_E3") (pintype "bidirectional"))
    )
    (net (code "92") (name "/VA_ADC") (class "Default")
      (node (ref "U6") (pin "R7") (pinfunction "PA6_R7") (pintype "bidirectional"))
    )
    (net (code "93") (name "/VB_ADC") (class "Default")
      (node (ref "U6") (pin "R6") (pinfunction "PC4_R6") (pintype "bidirectional"))
    )
    (net (code "94") (name "/VCP_RX") (class "Default")
      (node (ref "R124") (pin "1") (pintype "passive"))
      (node (ref "U6") (pin "C6") (pinfunction "PB5_C6") (pintype "bidirectional"))
    )
    (net (code "95") (name "/VCP_TX") (class "Default")
      (node (ref "R119") (pin "1") (pintype "passive"))
      (node (ref "U6") (pin "A5") (pinfunction "PB6_A5") (pintype "bidirectional"))
    )
    (net (code "96") (name "/VC_ADC") (class "Default")
      (node (ref "U6") (pin "M8") (pinfunction "PB1_M8") (pintype "bidirectional"))
    )
    (net (code "97") (name "/VDSA_ADC") (class "Default")
      (node (ref "U6") (pin "P11") (pinfunction "PF12_P11") (pintype "bidirectional"))
    )
    (net (code "98") (name "/VDSB_ADC") (class "Default")
      (node (ref "U6") (pin "R8") (pinfunction "PB0_R8") (pintype "bidirectional"))
    )
    (net (code "99") (name "/VDSC_ADC") (class "Default")
      (node (ref "U6") (pin "M2") (pinfunction "PC3_M2") (pintype "bidirectional"))
    )
    (net (code "100") (name "/nBUTTON") (class "Default")
      (node (ref "C62") (pin "1") (pintype "passive"))
      (node (ref "D3") (pin "K") (pinfunction "K_K") (pintype "passive"))
      (node (ref "J3") (pin "18") (pinfunction "18_18") (pintype "passive"))
      (node (ref "R62") (pin "1") (pintype "passive"))
      (node (ref "R67") (pin "1") (pintype "passive"))
      (node (ref "R68") (pin "1") (pintype "passive"))
      (node (ref "U6") (pin "H15") (pinfunction "PD13_H15") (pintype "bidirectional"))
    )
    (net (code "101") (name "/nRST") (class "Default")
      (node (ref "C52") (pin "1") (pintype "passive"))
      (node (ref "R100") (pin "1") (pintype "passive"))
      (node (ref "R40") (pin "1") (pintype "passive"))
      (node (ref "U6") (pin "L1") (pinfunction "NRST_L1") (pintype "bidirectional"))
    )
    (net (code "109") (name "3V3") (class "Default")
      (node (ref "J3") (pin "1") (pinfunction "1_1") (pintype "passive"))
      (node (ref "LED10") (pin "A") (pinfunction "A_A") (pintype "passive"))
      (node (ref "LED8") (pin "A") (pinfunction "A_A") (pintype "passive"))
      (node (ref "LED9") (pin "A") (pinfunction "A_A") (pintype "passive"))
      (node (ref "R103") (pin "2") (pintype "passive"))
      (node (ref "R106") (pin "2") (pintype "passive"))
      (node (ref "R111") (pin "2") (pintype "passive"))
      (node (ref "R67") (pin "2") (pintype "passive"))
      (node (ref "R71") (pin "2") (pintype "passive"))
      (node (ref "R80") (pin "2") (pintype "passive"))
      (node (ref "R88") (pin "2") (pintype "passive"))
    )
    (net (code "110") (name "GND") (class "Default")
      (node (ref "C120") (pin "2") (pintype "passive"))
      (node (ref "C131") (pin "2") (pintype "passive"))
      (node (ref "C51") (pin "2") (pintype "passive"))
      (node (ref "C52") (pin "2") (pintype "passive"))
      (node (ref "C62") (pin "2") (pintype "passive"))
      (node (ref "D10") (pin "A") (pinfunction "A_A") (pintype "passive"))
      (node (ref "D14") (pin "A") (pinfunction "A_A") (pintype "passive"))
      (node (ref "D15") (pin "A") (pinfunction "A_A") (pintype "passive"))
      (node (ref "D16") (pin "A") (pinfunction "A_A") (pintype "passive"))
      (node (ref "D17") (pin "A") (pinfunction "A_A") (pintype "passive"))
      (node (ref "D18") (pin "A") (pinfunction "A_A") (pintype "passive"))
      (node (ref "D19") (pin "A") (pinfunction "A_A") (pintype "passive"))
      (node (ref "D20") (pin "A") (pinfunction "A_A") (pintype "passive"))
      (node (ref "D21") (pin "A") (pinfunction "A_A") (pintype "passive"))
      (node (ref "D22") (pin "A") (pinfunction "A_A") (pintype "passive"))
      (node (ref "D23") (pin "A") (pinfunction "A_A") (pintype "passive"))
      (node (ref "D3") (pin "A") (pinfunction "A_A") (pintype "passive"))
      (node (ref "D4") (pin "A") (pinfunction "A_A") (pintype "passive"))
      (node (ref "D5") (pin "A") (pinfunction "A_A") (pintype "passive"))
      (node (ref "D6") (pin "A") (pinfunction "A_A") (pintype "passive"))
      (node (ref "D7") (pin "A") (pinfunction "A_A") (pintype "passive"))
      (node (ref "D8") (pin "A") (pinfunction "A_A") (pintype "passive"))
      (node (ref "J3") (pin "14") (pinfunction "14_14") (pintype "passive"))
      (node (ref "J3") (pin "2") (pinfunction "2_2") (pintype "passive"))
      (node (ref "J3") (pin "MH1") (pinfunction "MH1_MH1") (pintype "passive"))
      (node (ref "J3") (pin "MH2") (pinfunction "MH2_MH2") (pintype "passive"))
      (node (ref "J3") (pin "MH3") (pinfunction "MH3_MH3") (pintype "passive"))
      (node (ref "J3") (pin "MH4") (pinfunction "MH4_MH4") (pintype "passive"))
      (node (ref "Q5") (pin "2") (pinfunction "S_2") (pintype "passive"))
      (node (ref "R5") (pin "1") (pintype "passive"))
      (node (ref "R92") (pin "1") (pintype "passive"))
      (node (ref "R95") (pin "1") (pintype "passive"))
      (node (ref "SW1") (pin "2") (pinfunction "2_2") (pintype "passive"))
      (node (ref "SW2") (pin "2") (pinfunction "2_2") (pintype "passive"))
      (node (ref "SW3") (pin "2") (pinfunction "2_2") (pintype "passive"))
    )
    (net (code "111") (name "Net-(C131-Pad1)") (class "Default")
      (node (ref "C131") (pin "1") (pintype "passive"))
      (node (ref "R109") (pin "1") (pintype "passive"))
    )
    (net (code "112") (name "Net-(D5-PadK)") (class "Default")
      (node (ref "D5") (pin "K") (pinfunction "K_K") (pintype "passive"))
      (node (ref "J3") (pin "12") (pinfunction "12_12") (pintype "passive"))
      (node (ref "R6") (pin "1") (pintype "passive"))
    )
    (net (code "113") (name "Net-(D6-PadK)") (class "Default")
      (node (ref "D6") (pin "K") (pinfunction "K_K") (pintype "passive"))
      (node (ref "J3") (pin "10") (pinfunction "10_10") (pintype "passive"))
      (node (ref "R7") (pin "1") (pintype "passive"))
    )
    (net (code "114") (name "Net-(D7-PadK)") (class "Default")
      (node (ref "D7") (pin "K") (pinfunction "K_K") (pintype "passive"))
      (node (ref "J3") (pin "8") (pinfunction "8_8") (pintype "passive"))
      (node (ref "R9") (pin "1") (pintype "passive"))
    )
    (net (code "115") (name "Net-(D8-PadK)") (class "Default")
      (node (ref "D8") (pin "K") (pinfunction "K_K") (pintype "passive"))
      (node (ref "J3") (pin "6") (pinfunction "6_6") (pintype "passive"))
      (node (ref "R10") (pin "1") (pintype "passive"))
    )
    (net (code "116") (name "Net-(D10-PadK)") (class "Default")
      (node (ref "D10") (pin "K") (pinfunction "K_K") (pintype "passive"))
      (node (ref "J3") (pin "4") (pinfunction "4_4") (pintype "passive"))
      (node (ref "R11") (pin "1") (pintype "passive"))
    )
    (net (code "117") (name "Net-(D16-PadK)") (class "Default")
      (node (ref "D16") (pin "K") (pinfunction "K_K") (pintype "passive"))
      (node (ref "J3") (pin "17") (pinfunction "17_17") (pintype "passive"))
      (node (ref "R93") (pin "2") (pintype "passive"))
    )
    (net (code "118") (name "Net-(D18-PadK)") (class "Default")
      (node (ref "D18") (pin "K") (pinfunction "K_K") (pintype "passive"))
      (node (ref "J3") (pin "13") (pinfunction "13_13") (pintype "passive"))
      (node (ref "R102") (pin "2") (pintype "passive"))
    )
    (net (code "119") (name "Net-(D19-PadK)") (class "Default")
      (node (ref "D19") (pin "K") (pinfunction "K_K") (pintype "passive"))
      (node (ref "J3") (pin "11") (pinfunction "11_11") (pintype "passive"))
      (node (ref "R105") (pin "2") (pintype "passive"))
    )
    (net (code "120") (name "Net-(D20-PadK)") (class "Default")
      (node (ref "D20") (pin "K") (pinfunction "K_K") (pintype "passive"))
      (node (ref "J3") (pin "9") (pinfunction "9_9") (pintype "passive"))
      (node (ref "R108") (pin "2") (pintype "passive"))
    )
    (net (code "121") (name "Net-(D21-PadK)") (class "Default")
      (node (ref "D21") (pin "K") (pinfunction "K_K") (pintype "passive"))
      (node (ref "J3") (pin "7") (pinfunction "7_7") (pintype "passive"))
      (node (ref "R110") (pin "2") (pintype "passive"))
    )
    (net (code "122") (name "Net-(D22-PadK)") (class "Default")
      (node (ref "D22") (pin "K") (pinfunction "K_K") (pintype "passive"))
      (node (ref "J3") (pin "5") (pinfunction "5_5") (pintype "passive"))
      (node (ref "R119") (pin "2") (pintype "passive"))
    )
    (net (code "123") (name "Net-(D23-PadK)") (class "Default")
      (node (ref "D23") (pin "K") (pinfunction "K_K") (pintype "passive"))
      (node (ref "J3") (pin "3") (pinfunction "3_3") (pintype "passive"))
      (node (ref "R124") (pin "2") (pintype "passive"))
    )
    (net (code "124") (name "Net-(LED8-PadK)") (class "Default")
      (node (ref "LED8") (pin "K") (pinfunction "K_K") (pintype "passive"))
      (node (ref "R68") (pin "2") (pintype "passive"))
    )
    (net (code "125") (name "Net-(LED9-PadK)") (class "Default")
      (node (ref "LED9") (pin "K") (pinfunction "K_K") (pintype "passive"))
      (node (ref "R70") (pin "1") (pintype "passive"))
    )
    (net (code "126") (name "Net-(LED10-PadK)") (class "Default")
      (node (ref "LED10") (pin "K") (pinfunction "K_K") (pintype "passive"))
      (node (ref "R72") (pin "1") (pintype "passive"))
    )
    (net (code "127") (name "Net-(Q5-G)") (class "Default")
      (node (ref "Q5") (pin "1") (pinfunction "G_1") (pintype "passive"))
      (node (ref "R94") (pin "2") (pintype "passive"))
      (node (ref "R95") (pin "2") (pintype "passive"))
    )
    (net (code "128") (name "Net-(R35-Pad2)") (class "Default")
      (node (ref "R35") (pin "2") (pintype "passive"))
      (node (ref "SW1") (pin "1") (pinfunction "1_1") (pintype "passive"))
    )
    (net (code "129") (name "Net-(R40-Pad2)") (class "Default")
      (node (ref "R40") (pin "2") (pintype "passive"))
      (node (ref "SW2") (pin "1") (pinfunction "1_1") (pintype "passive"))
    )
    (net (code "130") (name "Net-(R62-Pad2)") (class "Default")
      (node (ref "R62") (pin "2") (pintype "passive"))
      (node (ref "SW3") (pin "1") (pinfunction "1_1") (pintype "passive"))
    )
    (net (code "131") (name "unconnected-(U6A-PA1-PadP2)") (class "Default")
      (node (ref "U6") (pin "P2") (pinfunction "PA1_P2") (pintype "bidirectional"))
    )
    (net (code "132") (name "unconnected-(U6A-PA2-PadR2)") (class "Default")
      (node (ref "U6") (pin "R2") (pinfunction "PA2_R2") (pintype "bidirectional"))
    )
    (net (code "133") (name "unconnected-(U6A-PA3-PadN5)") (class "Default")
      (node (ref "U6") (pin "N5") (pinfunction "PA3_N5") (pintype "bidirectional"))
    )
    (net (code "134") (name "unconnected-(U6A-PA5-PadP6)") (class "Default")
      (node (ref "U6") (pin "P6") (pinfunction "PA5_P6") (pintype "bidirectional"))
    )
    (net (code "135") (name "unconnected-(U6A-PA7-PadN6)") (class "Default")
      (node (ref "U6") (pin "N6") (pinfunction "PA7_N6") (pintype "bidirectional"))
    )
    (net (code "136") (name "unconnected-(U6A-PA11-PadC15)") (class "Default")
      (node (ref "U6") (pin "C15") (pinfunction "PA11_C15") (pintype "bidirectional"))
    )
    (net (code "137") (name "unconnected-(U6A-PA12-PadB15)") (class "Default")
      (node (ref "U6") (pin "B15") (pinfunction "PA12_B15") (pintype "bidirectional"))
    )
    (net (code "138") (name "unconnected-(U6A-PB2-PadP7)") (class "Default")
      (node (ref "U6") (pin "P7") (pinfunction "PB2_P7") (pintype "bidirectional"))
    )
    (net (code "139") (name "unconnected-(U6A-PB13-PadL15)") (class "Default")
      (node (ref "U6") (pin "L15") (pinfunction "PB13_L15") (pintype "bidirectional"))
    )
    (net (code "140") (name "unconnected-(U6A-PB14-PadK15)") (class "Default")
      (node (ref "U6") (pin "K15") (pinfunction "PB14_K15") (pintype "bidirectional"))
    )
    (net (code "141") (name "unconnected-(U6A-PB15-PadK14)") (class "Default")
      (node (ref "U6") (pin "K14") (pinfunction "PB15_K14") (pintype "bidirectional"))
    )
    (net (code "142") (name "unconnected-(U6A-PC0-PadL2)") (class "Default")
      (node (ref "U6") (pin "L2") (pinfunction "PC0_L2") (pintype "bidirectional"))
    )
    (net (code "143") (name "unconnected-(U6A-PC1-PadL3)") (class "Default")
      (node (ref "U6") (pin "L3") (pinfunction "PC1_L3") (pintype "bidirectional"))
    )
    (net (code "144") (name "unconnected-(U6A-PC2-PadM1)") (class "Default")
      (node (ref "U6") (pin "M1") (pinfunction "PC2_M1") (pintype "bidirectional"))
    )
    (net (code "145") (name "unconnected-(U6A-PC2_C-PadN1)") (class "Default")
      (node (ref "U6") (pin "N1") (pinfunction "PC2_C_N1") (pintype "input"))
    )
    (net (code "146") (name "unconnected-(U6A-PC5-PadM7)") (class "Default")
      (node (ref "U6") (pin "M7") (pinfunction "PC5_M7") (pintype "bidirectional"))
    )
    (net (code "147") (name "unconnected-(U6A-PC13-PadC1)") (class "Default")
      (node (ref "U6") (pin "C1") (pinfunction "PC13_C1") (pintype "bidirectional"))
    )
    (net (code "148") (name "unconnected-(U6A-PC14-OSC32_IN-PadD2)") (class "Default")
      (node (ref "U6") (pin "D2") (pinfunction "PC14-OSC32_IN_D2") (pintype "bidirectional"))
    )
    (net (code "149") (name "unconnected-(U6A-PC15-OSC32_OUT-PadD1)") (class "Default")
      (node (ref "U6") (pin "D1") (pinfunction "PC15-OSC32_OUT_D1") (pintype "bidirectional"))
    )
    (net (code "150") (name "unconnected-(U6A-PD0-PadC10)") (class "Default")
      (node (ref "U6") (pin "C10") (pinfunction "PD0_C10") (pintype "bidirectional"))
    )
    (net (code "151") (name "unconnected-(U6A-PD1-PadA10)") (class "Default")
      (node (ref "U6") (pin "A10") (pinfunction "PD1_A10") (pintype "bidirectional"))
    )
    (net (code "152") (name "unconnected-(U6A-PD3-PadA9)") (class "Default")
      (node (ref "U6") (pin "A9") (pinfunction "PD3_A9") (pintype "bidirectional"))
    )
    (net (code "153") (name "unconnected-(U6A-PD4-PadC9)") (class "Default")
      (node (ref "U6") (pin "C9") (pinfunction "PD4_C9") (pintype "bidirectional"))
    )
    (net (code "154") (name "unconnected-(U6B-PE7-PadP9)") (class "Default")
      (node (ref "U6") (pin "P9") (pinfunction "PE7_P9") (pintype "bidirectional"))
    )
    (net (code "155") (name "unconnected-(U6B-PF0-PadF4)") (class "Default")
      (node (ref "U6") (pin "F4") (pinfunction "PF0_F4") (pintype "bidirectional"))
    )
    (net (code "156") (name "unconnected-(U6B-PF1-PadF3)") (class "Default")
      (node (ref "U6") (pin "F3") (pinfunction "PF1_F3") (pintype "bidirectional"))
    )
    (net (code "157") (name "unconnected-(U6B-PF2-PadG3)") (class "Default")
      (node (ref "U6") (pin "G3") (pinfunction "PF2_G3") (pintype "bidirectional"))
    )
    (net (code "158") (name "unconnected-(U6B-PF4-PadH2)") (class "Default")
      (node (ref "U6") (pin "H2") (pinfunction "PF4_H2") (pintype "bidirectional"))
    )
    (net (code "159") (name "unconnected-(U6B-PF6-PadH1)") (class "Default")
      (node (ref "U6") (pin "H1") (pinfunction "PF6_H1") (pintype "bidirectional"))
    )
    (net (code "160") (name "unconnected-(U6B-PF8-PadJ2)") (class "Default")
      (node (ref "U6") (pin "J2") (pinfunction "PF8_J2") (pintype "bidirectional"))
    )
    (net (code "161") (name "unconnected-(U6B-PF15-PadN10)") (class "Default")
      (node (ref "U6") (pin "N10") (pinfunction "PF15_N10") (pintype "bidirectional"))
    )
    (net (code "162") (name "unconnected-(U6B-PG0-PadP8)") (class "Default")
      (node (ref "U6") (pin "P8") (pinfunction "PG0_P8") (pintype "bidirectional"))
    )
    (net (code "163") (name "unconnected-(U6B-PG1-PadN9)") (class "Default")
      (node (ref "U6") (pin "N9") (pinfunction "PG1_N9") (pintype "bidirectional"))
    )
    (net (code "164") (name "unconnected-(U6B-PG9-PadA8)") (class "Default")
      (node (ref "U6") (pin "A8") (pinfunction "PG9_A8") (pintype "bidirectional"))
    )
    (net (code "165") (name "unconnected-(U6B-PG10-PadC8)") (class "Default")
      (node (ref "U6") (pin "C8") (pinfunction "PG10_C8") (pintype "bidirectional"))
    )
    (net (code "166") (name "unconnected-(U6B-PG15-PadD7)") (class "Default")
      (node (ref "U6") (pin "D7") (pinfunction "PG15_D7") (pintype "bidirectional"))
    )
    (net (code "167") (name "unconnected-(U6B-PH0-OSC_IN-PadJ1)") (class "Default")
      (node (ref "U6") (pin "J1") (pinfunction "PH0-OSC_IN_J1") (pintype "bidirectional"))
    )
    (net (code "168") (name "unconnected-(U6B-PH1-OSC_OUT-PadK1)") (class "Default")
      (node (ref "U6") (pin "K1") (pinfunction "PH1-OSC_OUT_K1") (pintype "bidirectional"))
    )
    (net (code "169") (name "unconnected-(U6B-PH2-PadN4)") (class "Default")
      (node (ref "U6") (pin "N4") (pinfunction "PH2_N4") (pintype "bidirectional"))
    )
    (net (code "170") (name "unconnected-(U6B-PH3-PadR4)") (class "Default")
      (node (ref "U6") (pin "R4") (pinfunction "PH3_R4") (pintype "bidirectional"))
    )
    (net (code "171") (name "unconnected-(U6B-PH4-PadP4)") (class "Default")
      (node (ref "U6") (pin "P4") (pinfunction "PH4_P4") (pintype "bidirectional"))
    )
    (net (code "172") (name "unconnected-(U6B-PH9-PadM14)") (class "Default")
      (node (ref "U6") (pin "M14") (pinfunction "PH9_M14") (pintype "bidirectional"))
    )
    (net (code "173") (name "unconnected-(U6B-PH14-PadB12)") (class "Default")
      (node (ref "U6") (pin "B12") (pinfunction "PH14_B12") (pintype "bidirectional"))
    )
    (net (code "174") (name "unconnected-(U6B-PH15-PadD12)") (class "Default")
      (node (ref "U6") (pin "D12") (pinfunction "PH15_D12") (pintype "bidirectional"))
    )
  )
)
